# KSZ8851SNL.net
KiCad netlist of a schematic drawn in Altium Designer
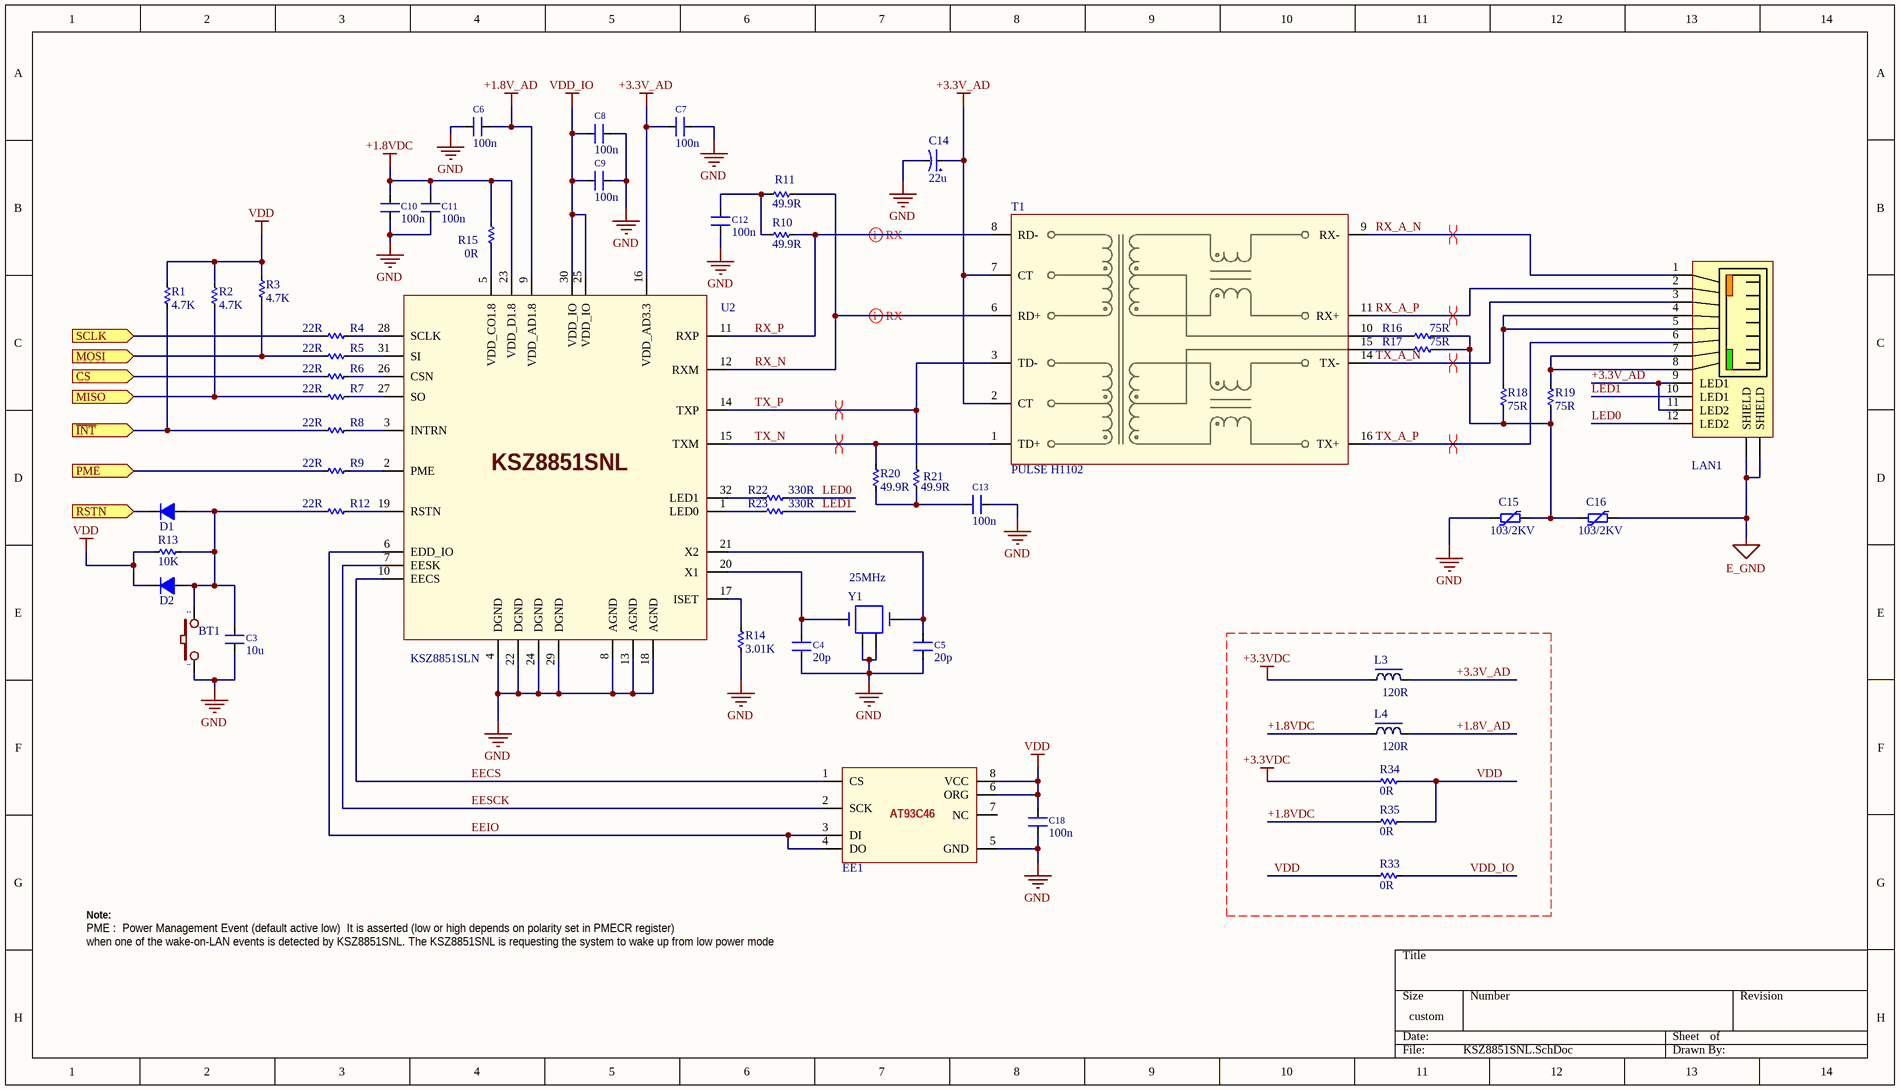
[diagram p0: KSZ8851SNL.SchDoc]

(export (version "E")
  (design (tool "Eeschema 10.0.6"))
  (components
    (comp (ref "BT1")
      (value "BUTTON1")
      (footprint "SW-SMD - 3x4")
      (libsource (lib "Sang_Library") (part "BUTTON1"))
    )
    (comp (ref "C3")
      (value "10u")
      (footprint "CN-SMD-1206")
      (description "CAP SMD")
      (fields (field (name "DESIGNED BY") "VanDungEvn"))
      (libsource (lib "Sang_Library") (part "CAP SMD"))
    )
    (comp (ref "C4")
      (value "20p")
      (footprint "CN-SMD-0603")
      (description "CAP SMD")
      (fields (field (name "DESIGNED BY") "VanDungEvn"))
      (libsource (lib "Sang_Library") (part "CAP SMD"))
    )
    (comp (ref "C5")
      (value "20p")
      (footprint "CN-SMD-0603")
      (description "CAP SMD")
      (fields (field (name "DESIGNED BY") "VanDungEvn"))
      (libsource (lib "Sang_Library") (part "CAP SMD"))
    )
    (comp (ref "C6")
      (value "100n")
      (footprint "CN-SMD-0805")
      (description "CAP SMD")
      (fields (field (name "DESIGNED BY") "VanDungEvn"))
      (libsource (lib "Sang_Library") (part "CAP SMD"))
    )
    (comp (ref "C7")
      (value "100n")
      (footprint "CN-SMD-0805")
      (description "CAP SMD")
      (fields (field (name "DESIGNED BY") "VanDungEvn"))
      (libsource (lib "Sang_Library") (part "CAP SMD"))
    )
    (comp (ref "C8")
      (value "100n")
      (footprint "CN-SMD-0805")
      (description "CAP SMD")
      (fields (field (name "DESIGNED BY") "VanDungEvn"))
      (libsource (lib "Sang_Library") (part "CAP SMD"))
    )
    (comp (ref "C9")
      (value "100n")
      (footprint "CN-SMD-0805")
      (description "CAP SMD")
      (fields (field (name "DESIGNED BY") "VanDungEvn"))
      (libsource (lib "Sang_Library") (part "CAP SMD"))
    )
    (comp (ref "C10")
      (value "100n")
      (footprint "CN-SMD-0805")
      (description "CAP SMD")
      (fields (field (name "DESIGNED BY") "VanDungEvn"))
      (libsource (lib "Sang_Library") (part "CAP SMD"))
    )
    (comp (ref "C11")
      (value "100n")
      (footprint "CN-SMD-0805")
      (description "CAP SMD")
      (fields (field (name "DESIGNED BY") "VanDungEvn"))
      (libsource (lib "Sang_Library") (part "CAP SMD"))
    )
    (comp (ref "C12")
      (value "100n")
      (footprint "CN-SMD-0805")
      (description "CAP SMD")
      (fields (field (name "DESIGNED BY") "VanDungEvn"))
      (libsource (lib "Sang_Library") (part "CAP SMD"))
    )
    (comp (ref "C13")
      (value "100n")
      (footprint "CN-SMD-0805")
      (description "CAP SMD")
      (fields (field (name "DESIGNED BY") "VanDungEvn"))
      (libsource (lib "Sang_Library") (part "CAP SMD"))
    )
    (comp (ref "C14")
      (value "22u")
      (footprint "CAP-ALU-SMD-5.5x5.5")
      (description "CAP-ALU-SMD")
      (fields (field (name "PUBLISHER") "Altium Limited"))
      (libsource (lib "Sang_Library") (part "CAP-ALU-SMD"))
    )
    (comp (ref "C15") (value "103/2KV") (footprint "MOV-7D") (libsource (lib "Huan") (part "MOV")))
    (comp (ref "C16") (value "103/2KV") (footprint "MOV-7D") (libsource (lib "Huan") (part "MOV")))
    (comp (ref "C18")
      (value "100n")
      (footprint "CN-SMD-0805")
      (description "CAP SMD")
      (fields (field (name "DESIGNED BY") "VanDungEvn"))
      (libsource (lib "Sang_Library") (part "CAP SMD"))
    )
    (comp (ref "D1")
      (value "Diode  1N4007")
      (footprint "SOD-123")
      (description "Diode 1A")
      (libsource (lib "Sang_Library") (part "Diode  1N4007"))
    )
    (comp (ref "D2")
      (value "Diode  1N4007")
      (footprint "SOD-123")
      (description "Diode 1A")
      (libsource (lib "Sang_Library") (part "Diode  1N4007"))
    )
    (comp (ref "EE1")
      (value "AT93C46D")
      (footprint "SOP-8_mini")
      (description "3-wire Serial EEPROM")
      (libsource (lib "Huan") (part "AT93C46D"))
    )
    (comp (ref "L3")
      (value "120R")
      (footprint "IN-SMD-0603")
      (description "inductor-SMD")
      (libsource (lib "Sang_Library") (part "inductor-SMD"))
    )
    (comp (ref "L4")
      (value "120R")
      (footprint "IN-SMD-0603")
      (description "inductor-SMD")
      (libsource (lib "Sang_Library") (part "inductor-SMD"))
    )
    (comp (ref "LAN1")
      (value "RJHSE-5381")
      (footprint "RJ45")
      (description "https://pdf1.alldatasheet.com/datasheet-pdf/view/585698/AMPHENOL/RJHSE-5381.html")
      (libsource (lib "Huan") (part "RJHSE-5381"))
    )
    (comp (ref "R1")
      (value "4.7K")
      (footprint "RES-SMD-0603")
      (description "Resistor")
      (fields
        (field (name "MANUFACTURER") "Generic Components")
        (field (name "PUBLISHER") "Altium Hobart Technology Centre")
      )
      (libsource (lib "Sang_Library") (part "Res-SMD"))
    )
    (comp (ref "R2")
      (value "4.7K")
      (footprint "RES-SMD-0603")
      (description "Resistor")
      (fields
        (field (name "MANUFACTURER") "Generic Components")
        (field (name "PUBLISHER") "Altium Hobart Technology Centre")
      )
      (libsource (lib "Sang_Library") (part "Res-SMD"))
    )
    (comp (ref "R3")
      (value "4.7K")
      (footprint "RES-SMD-0603")
      (description "Resistor")
      (fields
        (field (name "MANUFACTURER") "Generic Components")
        (field (name "PUBLISHER") "Altium Hobart Technology Centre")
      )
      (libsource (lib "Sang_Library") (part "Res-SMD"))
    )
    (comp (ref "R4")
      (value "22R")
      (footprint "RES-SMD-0603")
      (description "Resistor")
      (fields
        (field (name "MANUFACTURER") "Generic Components")
        (field (name "PUBLISHER") "Altium Hobart Technology Centre")
      )
      (libsource (lib "Sang_Library") (part "Res-SMD"))
    )
    (comp (ref "R5")
      (value "22R")
      (footprint "RES-SMD-0603")
      (description "Resistor")
      (fields
        (field (name "MANUFACTURER") "Generic Components")
        (field (name "PUBLISHER") "Altium Hobart Technology Centre")
      )
      (libsource (lib "Sang_Library") (part "Res-SMD"))
    )
    (comp (ref "R6")
      (value "22R")
      (footprint "RES-SMD-0603")
      (description "Resistor")
      (fields
        (field (name "MANUFACTURER") "Generic Components")
        (field (name "PUBLISHER") "Altium Hobart Technology Centre")
      )
      (libsource (lib "Sang_Library") (part "Res-SMD"))
    )
    (comp (ref "R7")
      (value "22R")
      (footprint "RES-SMD-0603")
      (description "Resistor")
      (fields
        (field (name "MANUFACTURER") "Generic Components")
        (field (name "PUBLISHER") "Altium Hobart Technology Centre")
      )
      (libsource (lib "Sang_Library") (part "Res-SMD"))
    )
    (comp (ref "R8")
      (value "22R")
      (footprint "RES-SMD-0603")
      (description "Resistor")
      (fields
        (field (name "MANUFACTURER") "Generic Components")
        (field (name "PUBLISHER") "Altium Hobart Technology Centre")
      )
      (libsource (lib "Sang_Library") (part "Res-SMD"))
    )
    (comp (ref "R9")
      (value "22R")
      (footprint "RES-SMD-0603")
      (description "Resistor")
      (fields
        (field (name "MANUFACTURER") "Generic Components")
        (field (name "PUBLISHER") "Altium Hobart Technology Centre")
      )
      (libsource (lib "Sang_Library") (part "Res-SMD"))
    )
    (comp (ref "R10")
      (value "49.9R")
      (footprint "RES-SMD-0805")
      (description "Resistor")
      (fields
        (field (name "MANUFACTURER") "Generic Components")
        (field (name "PUBLISHER") "Altium Hobart Technology Centre")
      )
      (libsource (lib "Sang_Library") (part "Res-SMD"))
    )
    (comp (ref "R11")
      (value "49.9R")
      (footprint "RES-SMD-0805")
      (description "Resistor")
      (fields
        (field (name "MANUFACTURER") "Generic Components")
        (field (name "PUBLISHER") "Altium Hobart Technology Centre")
      )
      (libsource (lib "Sang_Library") (part "Res-SMD"))
    )
    (comp (ref "R12")
      (value "22R")
      (footprint "RES-SMD-0603")
      (description "Resistor")
      (fields
        (field (name "MANUFACTURER") "Generic Components")
        (field (name "PUBLISHER") "Altium Hobart Technology Centre")
      )
      (libsource (lib "Sang_Library") (part "Res-SMD"))
    )
    (comp (ref "R13")
      (value "10K")
      (footprint "RES-SMD-0603")
      (description "Resistor")
      (fields
        (field (name "MANUFACTURER") "Generic Components")
        (field (name "PUBLISHER") "Altium Hobart Technology Centre")
      )
      (libsource (lib "Sang_Library") (part "Res-SMD"))
    )
    (comp (ref "R14")
      (value "3.01K")
      (footprint "RES-SMD-0603")
      (description "Resistor")
      (fields
        (field (name "MANUFACTURER") "Generic Components")
        (field (name "PUBLISHER") "Altium Hobart Technology Centre")
      )
      (libsource (lib "Sang_Library") (part "Res-SMD"))
    )
    (comp (ref "R15")
      (value "0R")
      (footprint "RES-SMD-0603")
      (description "Resistor")
      (fields
        (field (name "MANUFACTURER") "Generic Components")
        (field (name "PUBLISHER") "Altium Hobart Technology Centre")
      )
      (libsource (lib "Sang_Library") (part "Res-SMD"))
    )
    (comp (ref "R16")
      (value "75R")
      (footprint "RES-SMD-0805")
      (description "Resistor")
      (fields
        (field (name "MANUFACTURER") "Generic Components")
        (field (name "PUBLISHER") "Altium Hobart Technology Centre")
      )
      (libsource (lib "Sang_Library") (part "Res-SMD"))
    )
    (comp (ref "R17")
      (value "75R")
      (footprint "RES-SMD-0805")
      (description "Resistor")
      (fields
        (field (name "MANUFACTURER") "Generic Components")
        (field (name "PUBLISHER") "Altium Hobart Technology Centre")
      )
      (libsource (lib "Sang_Library") (part "Res-SMD"))
    )
    (comp (ref "R18")
      (value "75R")
      (footprint "RES-SMD-0805")
      (description "Resistor")
      (fields
        (field (name "MANUFACTURER") "Generic Components")
        (field (name "PUBLISHER") "Altium Hobart Technology Centre")
      )
      (libsource (lib "Sang_Library") (part "Res-SMD"))
    )
    (comp (ref "R19")
      (value "75R")
      (footprint "RES-SMD-0805")
      (description "Resistor")
      (fields
        (field (name "MANUFACTURER") "Generic Components")
        (field (name "PUBLISHER") "Altium Hobart Technology Centre")
      )
      (libsource (lib "Sang_Library") (part "Res-SMD"))
    )
    (comp (ref "R20")
      (value "49.9R")
      (footprint "RES-SMD-0805")
      (description "Resistor")
      (fields
        (field (name "MANUFACTURER") "Generic Components")
        (field (name "PUBLISHER") "Altium Hobart Technology Centre")
      )
      (libsource (lib "Sang_Library") (part "Res-SMD"))
    )
    (comp (ref "R21")
      (value "49.9R")
      (footprint "RES-SMD-0805")
      (description "Resistor")
      (fields
        (field (name "MANUFACTURER") "Generic Components")
        (field (name "PUBLISHER") "Altium Hobart Technology Centre")
      )
      (libsource (lib "Sang_Library") (part "Res-SMD"))
    )
    (comp (ref "R22")
      (value "330R")
      (footprint "RES-SMD-0805")
      (description "Resistor")
      (fields
        (field (name "MANUFACTURER") "Generic Components")
        (field (name "PUBLISHER") "Altium Hobart Technology Centre")
      )
      (libsource (lib "Sang_Library") (part "Res-SMD"))
    )
    (comp (ref "R23")
      (value "330R")
      (footprint "RES-SMD-0805")
      (description "Resistor")
      (fields
        (field (name "MANUFACTURER") "Generic Components")
        (field (name "PUBLISHER") "Altium Hobart Technology Centre")
      )
      (libsource (lib "Sang_Library") (part "Res-SMD"))
    )
    (comp (ref "R33")
      (value "0R")
      (footprint "RES-SMD-0805")
      (description "Resistor")
      (fields
        (field (name "MANUFACTURER") "Generic Components")
        (field (name "PUBLISHER") "Altium Hobart Technology Centre")
      )
      (libsource (lib "Sang_Library") (part "Res-SMD"))
    )
    (comp (ref "R34")
      (value "0R")
      (footprint "RES-SMD-0805")
      (description "Resistor")
      (fields
        (field (name "MANUFACTURER") "Generic Components")
        (field (name "PUBLISHER") "Altium Hobart Technology Centre")
      )
      (libsource (lib "Sang_Library") (part "Res-SMD"))
    )
    (comp (ref "R35")
      (value "0R")
      (footprint "RES-SMD-0805")
      (description "Resistor")
      (fields
        (field (name "MANUFACTURER") "Generic Components")
        (field (name "PUBLISHER") "Altium Hobart Technology Centre")
      )
      (libsource (lib "Sang_Library") (part "Res-SMD"))
    )
    (comp (ref "T1")
      (value "PULSE H1102")
      (footprint "PULSE-H1102NL")
      (libsource (lib "Huan") (part "PULSE H1102"))
    )
    (comp (ref "U2") (value "KSZ8851SLN") (footprint "QFN32-32") (libsource (lib "Huan") (part "KSZ8851SLN")))
    (comp (ref "Y1")
      (value "25MHz")
      (footprint "Crystal 4 pin SMD 32x25")
      (description "Crystal Oscillator")
      (fields (field (name "PUBLISHER") "Altium Limited"))
      (libsource (lib "Sang_Library") (part "XTAL_4Pin SMD"))
    )
  )
  (nets
    (net (code "1") (name "+1.8VDC") (class "Default")
      (node (ref "C10") (pin "1") (pinfunction "1_1") (pintype "passive"))
      (node (ref "C11") (pin "1") (pinfunction "1_1") (pintype "passive"))
      (node (ref "L4") (pin "1") (pinfunction "1_1") (pintype "passive"))
      (node (ref "R15") (pin "2") (pinfunction "2_2") (pintype "passive"))
      (node (ref "R35") (pin "1") (pinfunction "1_1") (pintype "passive"))
      (node (ref "U2") (pin "23") (pinfunction "VDD_D1.8_23") (pintype "passive"))
    )
    (net (code "2") (name "+1.8V_AD") (class "Default")
      (node (ref "C6") (pin "2") (pinfunction "2_2") (pintype "passive"))
      (node (ref "L4") (pin "2") (pinfunction "2_2") (pintype "passive"))
      (node (ref "U2") (pin "9") (pinfunction "VDD_AD1.8_9") (pintype "passive"))
    )
    (net (code "3") (name "+3.3VDC") (class "Default")
      (node (ref "L3") (pin "1") (pinfunction "1_1") (pintype "passive"))
      (node (ref "R34") (pin "1") (pinfunction "1_1") (pintype "passive"))
    )
    (net (code "4") (name "+3.3V_AD") (class "Default")
      (node (ref "C14") (pin "1") (pinfunction "1_1") (pintype "passive"))
      (node (ref "C7") (pin "1") (pinfunction "1_1") (pintype "passive"))
      (node (ref "L3") (pin "2") (pinfunction "2_2") (pintype "passive"))
      (node (ref "LAN1") (pin "11") (pinfunction "LED2_11") (pintype "passive"))
      (node (ref "LAN1") (pin "9") (pinfunction "LED1_9") (pintype "passive"))
      (node (ref "T1") (pin "2") (pinfunction "CT_2") (pintype "passive"))
      (node (ref "T1") (pin "7") (pinfunction "CT_7") (pintype "passive"))
      (node (ref "U2") (pin "16") (pinfunction "VDD_AD3.3_16") (pintype "passive"))
    )
    (net (code "5") (name "/CS") (class "Default")
      (node (ref "R6") (pin "1") (pinfunction "1_1") (pintype "passive"))
    )
    (net (code "6") (name "/EECS") (class "Default")
      (node (ref "EE1") (pin "1") (pinfunction "CS_1") (pintype "passive"))
      (node (ref "U2") (pin "10") (pinfunction "EECS_10") (pintype "passive"))
    )
    (net (code "7") (name "/EEIO") (class "Default")
      (node (ref "EE1") (pin "3") (pinfunction "DI_3") (pintype "passive"))
      (node (ref "EE1") (pin "4") (pinfunction "DO_4") (pintype "passive"))
      (node (ref "U2") (pin "6") (pinfunction "EDD_IO_6") (pintype "passive"))
    )
    (net (code "8") (name "/EESCK") (class "Default")
      (node (ref "EE1") (pin "2") (pinfunction "SCK_2") (pintype "passive"))
      (node (ref "U2") (pin "7") (pinfunction "EESK_7") (pintype "passive"))
    )
    (net (code "9") (name "/LED0") (class "Default")
      (node (ref "LAN1") (pin "12") (pinfunction "LED2_12") (pintype "passive"))
      (node (ref "R22") (pin "2") (pinfunction "2_2") (pintype "passive"))
    )
    (net (code "10") (name "/LED1") (class "Default")
      (node (ref "LAN1") (pin "10") (pinfunction "LED1_10") (pintype "passive"))
      (node (ref "R23") (pin "2") (pinfunction "2_2") (pintype "passive"))
    )
    (net (code "11") (name "/MISO") (class "Default")
      (node (ref "R2") (pin "1") (pinfunction "1_1") (pintype "passive"))
      (node (ref "R7") (pin "1") (pinfunction "1_1") (pintype "passive"))
    )
    (net (code "12") (name "/MOSI") (class "Default")
      (node (ref "R3") (pin "1") (pinfunction "1_1") (pintype "passive"))
      (node (ref "R5") (pin "1") (pinfunction "1_1") (pintype "passive"))
    )
    (net (code "13") (name "/PME") (class "Default")
      (node (ref "R9") (pin "1") (pinfunction "1_1") (pintype "passive"))
    )
    (net (code "14") (name "/RSTN") (class "Default")
      (node (ref "D1") (pin "2") (pinfunction "2_2") (pintype "passive"))
    )
    (net (code "15") (name "/RX_A_N") (class "Default")
      (node (ref "LAN1") (pin "1") (pintype "passive"))
      (node (ref "T1") (pin "9") (pinfunction "RX-_9") (pintype "passive"))
    )
    (net (code "16") (name "/RX_A_P") (class "Default")
      (node (ref "LAN1") (pin "2") (pintype "passive"))
      (node (ref "T1") (pin "11") (pinfunction "RX+_11") (pintype "passive"))
    )
    (net (code "17") (name "/RX_N") (class "Default")
      (node (ref "R11") (pin "1") (pinfunction "1_1") (pintype "passive"))
      (node (ref "T1") (pin "6") (pinfunction "RD+_6") (pintype "passive"))
      (node (ref "U2") (pin "12") (pinfunction "RXM_12") (pintype "passive"))
    )
    (net (code "18") (name "/RX_P") (class "Default")
      (node (ref "R10") (pin "1") (pinfunction "1_1") (pintype "passive"))
      (node (ref "T1") (pin "8") (pinfunction "RD-_8") (pintype "passive"))
      (node (ref "U2") (pin "11") (pinfunction "RXP_11") (pintype "passive"))
    )
    (net (code "19") (name "/SCLK") (class "Default")
      (node (ref "R4") (pin "1") (pinfunction "1_1") (pintype "passive"))
    )
    (net (code "20") (name "/TX_A_N") (class "Default")
      (node (ref "LAN1") (pin "3") (pintype "passive"))
      (node (ref "T1") (pin "14") (pinfunction "TX-_14") (pintype "passive"))
    )
    (net (code "21") (name "/TX_A_P") (class "Default")
      (node (ref "LAN1") (pin "6") (pintype "passive"))
      (node (ref "T1") (pin "16") (pinfunction "TX+_16") (pintype "passive"))
    )
    (net (code "22") (name "/TX_N") (class "Default")
      (node (ref "R20") (pin "1") (pinfunction "1_1") (pintype "passive"))
      (node (ref "T1") (pin "1") (pinfunction "TD+_1") (pintype "passive"))
      (node (ref "U2") (pin "15") (pinfunction "TXM_15") (pintype "passive"))
    )
    (net (code "23") (name "/TX_P") (class "Default")
      (node (ref "R21") (pin "1") (pinfunction "1_1") (pintype "passive"))
      (node (ref "T1") (pin "3") (pinfunction "TD-_3") (pintype "passive"))
      (node (ref "U2") (pin "14") (pinfunction "TXP_14") (pintype "passive"))
    )
    (net (code "24") (name "/~{INT}") (class "Default")
      (node (ref "R1") (pin "1") (pinfunction "1_1") (pintype "passive"))
      (node (ref "R8") (pin "1") (pinfunction "1_1") (pintype "passive"))
    )
    (net (code "25") (name "E_GND") (class "Default")
      (node (ref "C16") (pin "2") (pinfunction "2_2") (pintype "passive"))
      (node (ref "LAN1") (pin "SHIELD") (pinfunction "SHIELD_SHIELD") (pintype "passive"))
    )
    (net (code "26") (name "GND") (class "Default")
      (node (ref "BT1") (pin "1") (pinfunction "1_1") (pintype "passive"))
      (node (ref "C10") (pin "2") (pinfunction "2_2") (pintype "passive"))
      (node (ref "C11") (pin "2") (pinfunction "2_2") (pintype "passive"))
      (node (ref "C12") (pin "2") (pinfunction "2_2") (pintype "passive"))
      (node (ref "C13") (pin "1") (pinfunction "1_1") (pintype "passive"))
      (node (ref "C14") (pin "2") (pinfunction "2_2") (pintype "passive"))
      (node (ref "C15") (pin "1") (pinfunction "1_1") (pintype "passive"))
      (node (ref "C18") (pin "2") (pinfunction "2_2") (pintype "passive"))
      (node (ref "C3") (pin "1") (pinfunction "1_1") (pintype "passive"))
      (node (ref "C4") (pin "1") (pinfunction "1_1") (pintype "passive"))
      (node (ref "C5") (pin "1") (pinfunction "1_1") (pintype "passive"))
      (node (ref "C6") (pin "1") (pinfunction "1_1") (pintype "passive"))
      (node (ref "C7") (pin "2") (pinfunction "2_2") (pintype "passive"))
      (node (ref "C8") (pin "2") (pinfunction "2_2") (pintype "passive"))
      (node (ref "C9") (pin "2") (pinfunction "2_2") (pintype "passive"))
      (node (ref "EE1") (pin "5") (pinfunction "GND_5") (pintype "passive"))
      (node (ref "R14") (pin "2") (pinfunction "2_2") (pintype "passive"))
      (node (ref "U2") (pin "13") (pinfunction "AGND_13") (pintype "passive"))
      (node (ref "U2") (pin "18") (pinfunction "AGND_18") (pintype "passive"))
      (node (ref "U2") (pin "22") (pinfunction "DGND_22") (pintype "passive"))
      (node (ref "U2") (pin "24") (pinfunction "DGND_24") (pintype "passive"))
      (node (ref "U2") (pin "29") (pinfunction "DGND_29") (pintype "passive"))
      (node (ref "U2") (pin "4") (pinfunction "DGND_4") (pintype "passive"))
      (node (ref "U2") (pin "8") (pinfunction "AGND_8") (pintype "passive"))
      (node (ref "Y1") (pin "2") (pinfunction "GND_2") (pintype "passive"))
      (node (ref "Y1") (pin "4") (pinfunction "GND_4") (pintype "passive"))
    )
    (net (code "27") (name "Net-(BT1-Pad2)") (class "Default")
      (node (ref "BT1") (pin "2") (pinfunction "2_2") (pintype "passive"))
      (node (ref "C3") (pin "2") (pinfunction "2_2") (pintype "passive"))
      (node (ref "D1") (pin "1") (pinfunction "1_1") (pintype "passive"))
      (node (ref "D2") (pin "1") (pinfunction "1_1") (pintype "passive"))
      (node (ref "R12") (pin "1") (pinfunction "1_1") (pintype "passive"))
      (node (ref "R13") (pin "1") (pinfunction "1_1") (pintype "passive"))
    )
    (net (code "28") (name "Net-(C12-Pad1)") (class "Default")
      (node (ref "C12") (pin "1") (pinfunction "1_1") (pintype "passive"))
      (node (ref "R10") (pin "2") (pinfunction "2_2") (pintype "passive"))
      (node (ref "R11") (pin "2") (pinfunction "2_2") (pintype "passive"))
    )
    (net (code "29") (name "Net-(C13-Pad2)") (class "Default")
      (node (ref "C13") (pin "2") (pinfunction "2_2") (pintype "passive"))
      (node (ref "R20") (pin "2") (pinfunction "2_2") (pintype "passive"))
      (node (ref "R21") (pin "2") (pinfunction "2_2") (pintype "passive"))
    )
    (net (code "30") (name "Net-(C15-Pad2)") (class "Default")
      (node (ref "C15") (pin "2") (pinfunction "2_2") (pintype "passive"))
      (node (ref "C16") (pin "1") (pinfunction "1_1") (pintype "passive"))
      (node (ref "R16") (pin "1") (pinfunction "1_1") (pintype "passive"))
      (node (ref "R17") (pin "1") (pinfunction "1_1") (pintype "passive"))
      (node (ref "R18") (pin "2") (pinfunction "2_2") (pintype "passive"))
      (node (ref "R19") (pin "2") (pinfunction "2_2") (pintype "passive"))
    )
    (net (code "31") (name "Net-(LAN1-Pad4)") (class "Default")
      (node (ref "LAN1") (pin "4") (pintype "passive"))
      (node (ref "LAN1") (pin "5") (pintype "passive"))
      (node (ref "R18") (pin "1") (pinfunction "1_1") (pintype "passive"))
    )
    (net (code "32") (name "Net-(LAN1-Pad7)") (class "Default")
      (node (ref "LAN1") (pin "7") (pintype "passive"))
      (node (ref "LAN1") (pin "8") (pintype "passive"))
      (node (ref "R19") (pin "1") (pinfunction "1_1") (pintype "passive"))
    )
    (net (code "33") (name "Net-(R16-Pad2)") (class "Default")
      (node (ref "R16") (pin "2") (pinfunction "2_2") (pintype "passive"))
      (node (ref "T1") (pin "10") (pintype "passive"))
    )
    (net (code "34") (name "Net-(R17-Pad2)") (class "Default")
      (node (ref "R17") (pin "2") (pinfunction "2_2") (pintype "passive"))
      (node (ref "T1") (pin "15") (pintype "passive"))
    )
    (net (code "35") (name "Net-(U2-CSN)") (class "Default")
      (node (ref "R6") (pin "2") (pinfunction "2_2") (pintype "passive"))
      (node (ref "U2") (pin "26") (pinfunction "CSN_26") (pintype "passive"))
    )
    (net (code "36") (name "Net-(U2-INTRN)") (class "Default")
      (node (ref "R8") (pin "2") (pinfunction "2_2") (pintype "passive"))
      (node (ref "U2") (pin "3") (pinfunction "INTRN_3") (pintype "passive"))
    )
    (net (code "37") (name "Net-(U2-ISET)") (class "Default")
      (node (ref "R14") (pin "1") (pinfunction "1_1") (pintype "passive"))
      (node (ref "U2") (pin "17") (pinfunction "ISET_17") (pintype "passive"))
    )
    (net (code "38") (name "Net-(U2-LED0)") (class "Default")
      (node (ref "R23") (pin "1") (pinfunction "1_1") (pintype "passive"))
      (node (ref "U2") (pin "1") (pinfunction "LED0_1") (pintype "passive"))
    )
    (net (code "39") (name "Net-(U2-LED1)") (class "Default")
      (node (ref "R22") (pin "1") (pinfunction "1_1") (pintype "passive"))
      (node (ref "U2") (pin "32") (pinfunction "LED1_32") (pintype "passive"))
    )
    (net (code "40") (name "Net-(U2-PME)") (class "Default")
      (node (ref "R9") (pin "2") (pinfunction "2_2") (pintype "passive"))
      (node (ref "U2") (pin "2") (pinfunction "PME_2") (pintype "passive"))
    )
    (net (code "41") (name "Net-(U2-RSTN)") (class "Default")
      (node (ref "R12") (pin "2") (pinfunction "2_2") (pintype "passive"))
      (node (ref "U2") (pin "19") (pinfunction "RSTN_19") (pintype "passive"))
    )
    (net (code "42") (name "Net-(U2-SCLK)") (class "Default")
      (node (ref "R4") (pin "2") (pinfunction "2_2") (pintype "passive"))
      (node (ref "U2") (pin "28") (pinfunction "SCLK_28") (pintype "passive"))
    )
    (net (code "43") (name "Net-(U2-SI)") (class "Default")
      (node (ref "R5") (pin "2") (pinfunction "2_2") (pintype "passive"))
      (node (ref "U2") (pin "31") (pinfunction "SI_31") (pintype "passive"))
    )
    (net (code "44") (name "Net-(U2-SO)") (class "Default")
      (node (ref "R7") (pin "2") (pinfunction "2_2") (pintype "passive"))
      (node (ref "U2") (pin "27") (pinfunction "SO_27") (pintype "passive"))
    )
    (net (code "45") (name "Net-(U2-VDD_CO1.8)") (class "Default")
      (node (ref "R15") (pin "1") (pinfunction "1_1") (pintype "passive"))
      (node (ref "U2") (pin "5") (pinfunction "VDD_CO1.8_5") (pintype "passive"))
    )
    (net (code "46") (name "Net-(U2-X1)") (class "Default")
      (node (ref "C4") (pin "2") (pinfunction "2_2") (pintype "passive"))
      (node (ref "U2") (pin "20") (pinfunction "X1_20") (pintype "passive"))
      (node (ref "Y1") (pin "1") (pinfunction "OSC1_1") (pintype "passive"))
    )
    (net (code "47") (name "Net-(U2-X2)") (class "Default")
      (node (ref "C5") (pin "2") (pinfunction "2_2") (pintype "passive"))
      (node (ref "U2") (pin "21") (pinfunction "X2_21") (pintype "passive"))
      (node (ref "Y1") (pin "3") (pinfunction "OSC2_3") (pintype "passive"))
    )
    (net (code "48") (name "VDD") (class "Default")
      (node (ref "C18") (pin "1") (pinfunction "1_1") (pintype "passive"))
      (node (ref "D2") (pin "2") (pinfunction "2_2") (pintype "passive"))
      (node (ref "EE1") (pin "6") (pinfunction "ORG_6") (pintype "passive"))
      (node (ref "EE1") (pin "8") (pinfunction "VCC_8") (pintype "passive"))
      (node (ref "R1") (pin "2") (pinfunction "2_2") (pintype "passive"))
      (node (ref "R13") (pin "2") (pinfunction "2_2") (pintype "passive"))
      (node (ref "R2") (pin "2") (pinfunction "2_2") (pintype "passive"))
      (node (ref "R3") (pin "2") (pinfunction "2_2") (pintype "passive"))
      (node (ref "R33") (pin "1") (pinfunction "1_1") (pintype "passive"))
      (node (ref "R34") (pin "2") (pinfunction "2_2") (pintype "passive"))
      (node (ref "R35") (pin "2") (pinfunction "2_2") (pintype "passive"))
    )
    (net (code "49") (name "VDD_IO") (class "Default")
      (node (ref "C8") (pin "1") (pinfunction "1_1") (pintype "passive"))
      (node (ref "C9") (pin "1") (pinfunction "1_1") (pintype "passive"))
      (node (ref "R33") (pin "2") (pinfunction "2_2") (pintype "passive"))
      (node (ref "U2") (pin "25") (pinfunction "_VDD_IO_25") (pintype "passive"))
      (node (ref "U2") (pin "30") (pinfunction "VDD_IO_30") (pintype "passive"))
    )
    (net (code "50") (name "unconnected-(EE1-NC-Pad7)") (class "Default")
      (node (ref "EE1") (pin "7") (pinfunction "NC_7") (pintype "passive"))
    )
  )
)
